# Air_Fryer_Coffee_Roaster_V1_0_2022_11_22.net
KiCad netlist of a schematic drawn in EAGLE
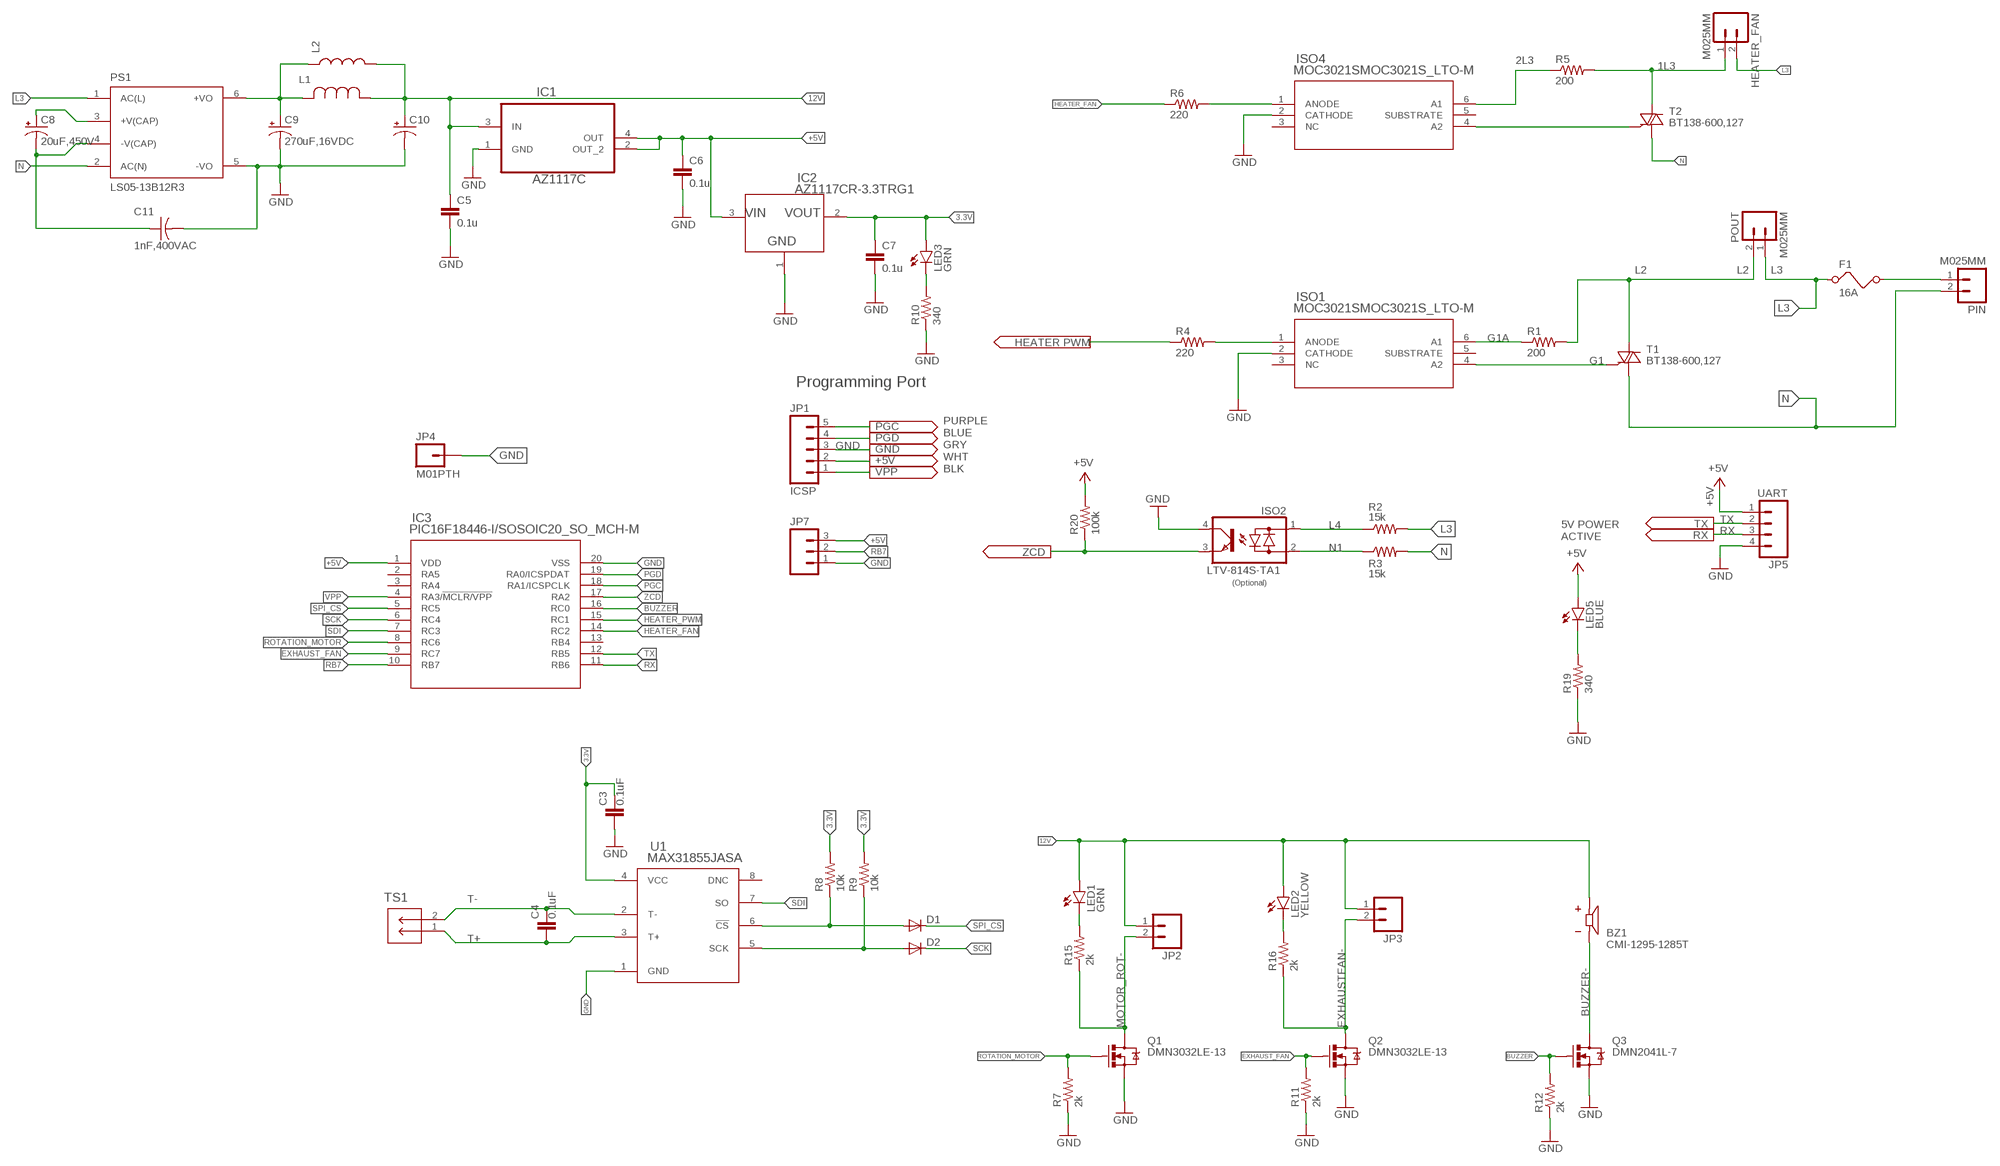
[diagram p0: schematic, sheet 1]

(export (version "E")
  (design (tool "Eeschema 10.0.6"))
  (components
    (comp (ref "BZ1")
      (value "CMI-1295-1285T")
      (footprint "eagle-import:CUI_CMI-1295-1285T")
      (fields (field (name "MF") "CUI Devices"))
      (libsource (lib "eagle-import") (part "CMI-1295-1285T"))
    )
    (comp (ref "C3")
      (value "0.1uF")
      (footprint "eagle-import:0805")
      (libsource (lib "eagle-import") (part "SparkFun-Capacitors_CAP0805"))
    )
    (comp (ref "C4")
      (value "0.1uF")
      (footprint "eagle-import:0805")
      (libsource (lib "eagle-import") (part "SparkFun-Capacitors_CAP0805"))
    )
    (comp (ref "C5")
      (value "0.1u")
      (footprint "eagle-import:1206")
      (libsource (lib "eagle-import") (part "CAP1206"))
    )
    (comp (ref "C6")
      (value "0.1u")
      (footprint "eagle-import:1206")
      (libsource (lib "eagle-import") (part "CAP1206"))
    )
    (comp (ref "C7")
      (value "0.1u")
      (footprint "eagle-import:1206")
      (libsource (lib "eagle-import") (part "CAP1206"))
    )
    (comp (ref "C8")
      (value "20uF,450V")
      (footprint "eagle-import:E5-13")
      (libsource (lib "eagle-import") (part "CPOL-USE5-13"))
    )
    (comp (ref "C9")
      (value "270uF,16VDC")
      (footprint "eagle-import:PANASONIC_E")
      (libsource (lib "eagle-import") (part "CAP_POLE"))
    )
    (comp (ref "C10")
      (value "CAP_POLE")
      (footprint "eagle-import:PANASONIC_E")
      (libsource (lib "eagle-import") (part "CAP_POLE"))
    )
    (comp (ref "C11")
      (value "1nF,400VAC")
      (footprint "eagle-import:C050-075X075")
      (libsource (lib "eagle-import") (part "C-US050-075X075"))
    )
    (comp (ref "D1")
      (value "DIODESOD-323F")
      (footprint "eagle-import:SOD-323F")
      (libsource (lib "eagle-import") (part "DIODESOD-323F"))
    )
    (comp (ref "D2")
      (value "DIODESOD-323F")
      (footprint "eagle-import:SOD-323F")
      (libsource (lib "eagle-import") (part "DIODESOD-323F"))
    )
    (comp (ref "F1")
      (value "16A")
      (footprint "eagle-import:FUSE")
      (libsource (lib "eagle-import") (part "FUSE"))
    )
    (comp (ref "HEATER_FAN")
      (value "M025MM")
      (footprint "eagle-import:SCREWTERMINAL-5MM-2")
      (libsource (lib "eagle-import") (part "SparkFun-Connectors_M025MM"))
    )
    (comp (ref "IC1")
      (value "AZ1117C")
      (footprint "eagle-import:SOT230P700X180-4N")
      (fields (field (name "MPN") "ADP3338AKCZ-5-R7"))
      (libsource (lib "eagle-import") (part "ADP3338AKCZ-5-R7"))
    )
    (comp (ref "IC2")
      (value "AZ1117CR-3.3TRG1")
      (footprint "eagle-import:SOT89_AZ1117_DIO")
      (fields (field (name "COPYRIGHT") "Copyright (C) 2022 Ultra Librarian. All rights reserved."))
      (libsource (lib "eagle-import") (part "AZ1117CR-3.3TRG1"))
    )
    (comp (ref "IC3")
      (value "PIC16F18446-I/SOSOIC20_SO_MCH-M")
      (footprint "eagle-import:SOIC20_SO_MCH-M")
      (fields
        (field (name "MANUFACTURER_PART_NUMBER") "PIC16F18446-I/SO")
        (field (name "COPYRIGHT") "Copyright (C) 2022 Ultra Librarian. All rights reserved.")
      )
      (libsource (lib "eagle-import") (part "PIC16F18446-I/SOSOIC20_SO_MCH-M"))
    )
    (comp (ref "ISO1")
      (value "MOC3021SMOC3021S_LTO-M")
      (footprint "eagle-import:MOC3021S_LTO-M")
      (fields
        (field (name "MANUFACTURER_PART_NUMBER") "MOC3021S")
        (field (name "COPYRIGHT") "Copyright (C) 2018 Accelerated Designs. All rights reserved")
      )
      (libsource (lib "eagle-import") (part "MOC3021SMOC3021S_LTO-M"))
    )
    (comp (ref "ISO2")
      (value "LTV-814S-TA1")
      (footprint "eagle-import:DIL4-SMD")
      (fields (field (name "MF") "VISHAY/TELEFUNKEN") (field (name "MPN") "SFH6206-3"))
      (libsource (lib "eagle-import") (part "SFH6206"))
    )
    (comp (ref "ISO4")
      (value "MOC3021SMOC3021S_LTO-M")
      (footprint "eagle-import:MOC3021S_LTO-M")
      (fields
        (field (name "MANUFACTURER_PART_NUMBER") "MOC3021S")
        (field (name "COPYRIGHT") "Copyright (C) 2018 Accelerated Designs. All rights reserved")
      )
      (libsource (lib "eagle-import") (part "MOC3021SMOC3021S_LTO-M"))
    )
    (comp (ref "JP1")
      (value "ICSP")
      (footprint "eagle-import:1X05")
      (libsource (lib "eagle-import") (part "M05PTH"))
    )
    (comp (ref "JP2")
      (value "M02POLAR_LOCK")
      (footprint "eagle-import:MOLEX-1X2_LOCK")
      (libsource (lib "eagle-import") (part "M02POLAR_LOCK"))
    )
    (comp (ref "JP3")
      (value "M02POLAR_LOCK")
      (footprint "eagle-import:MOLEX-1X2_LOCK")
      (libsource (lib "eagle-import") (part "M02POLAR_LOCK"))
    )
    (comp (ref "JP4")
      (value "M01PTH")
      (footprint "eagle-import:1X01")
      (libsource (lib "eagle-import") (part "M01PTH"))
    )
    (comp (ref "JP5")
      (value "UART")
      (footprint "eagle-import:1X04_LOCK")
      (libsource (lib "eagle-import") (part "M04LOCK"))
    )
    (comp (ref "JP7")
      (value "M03LOCK")
      (footprint "eagle-import:1X03_LOCK")
      (libsource (lib "eagle-import") (part "M03LOCK"))
    )
    (comp (ref "L1")
      (value "4.7uH, 2.2A")
      (footprint "eagle-import:IND_BOURNS_SRR1260")
      (fields
        (field (name "MANUFACTURER_PART_NUMBER") "SRR1260-100M")
        (field (name "COPYRIGHT") "Copyright (C) 2021 Ultra Librarian. All rights reserved.")
      )
      (libsource (lib "eagle-import") (part "SRR1260-100M"))
    )
    (comp (ref "L2")
      (value "INDUCTORCR54")
      (footprint "eagle-import:CR54")
      (libsource (lib "eagle-import") (part "INDUCTORCR54"))
    )
    (comp (ref "LED1")
      (value "GRN")
      (footprint "eagle-import:LED-1206")
      (libsource (lib "eagle-import") (part "LED1206"))
    )
    (comp (ref "LED2")
      (value "YELLOW")
      (footprint "eagle-import:LED-1206")
      (libsource (lib "eagle-import") (part "LED1206"))
    )
    (comp (ref "LED3")
      (value "GRN")
      (footprint "eagle-import:LED-1206")
      (libsource (lib "eagle-import") (part "LED1206"))
    )
    (comp (ref "LED5")
      (value "BLUE")
      (footprint "eagle-import:LED-1206")
      (libsource (lib "eagle-import") (part "LED1206"))
    )
    (comp (ref "PIN")
      (value "M025MM")
      (footprint "eagle-import:SCREWTERMINAL-5MM-2")
      (libsource (lib "eagle-import") (part "SparkFun-Connectors_M025MM"))
    )
    (comp (ref "POUT")
      (value "M025MM")
      (footprint "eagle-import:SCREWTERMINAL-5MM-2")
      (libsource (lib "eagle-import") (part "SparkFun-Connectors_M025MM"))
    )
    (comp (ref "PS1")
      (value "LS05-13B12R3")
      (footprint "eagle-import:CONV_LS05-13B12R3")
      (fields
        (field (name "DIGI-KEY_PART_NUMBER") "2725-LS05-13B12R3-ND")
        (field (name "MF") "Mornsun America, LLC")
      )
      (libsource (lib "eagle-import") (part "LS05-13B12R3"))
    )
    (comp (ref "Q1")
      (value "DMN3032LE-13")
      (footprint "eagle-import:SOT223")
      (libsource (lib "eagle-import") (part "NFET_SOT_223"))
    )
    (comp (ref "Q2")
      (value "DMN3032LE-13")
      (footprint "eagle-import:SOT223")
      (libsource (lib "eagle-import") (part "NFET_SOT_223"))
    )
    (comp (ref "Q3")
      (value "DMN2041L-7")
      (footprint "eagle-import:SOT23-3")
      (libsource (lib "eagle-import") (part "MOSFET-NCHANNELBSS123LT1G"))
    )
    (comp (ref "R1")
      (value "200")
      (footprint "eagle-import:R2512")
      (libsource (lib "eagle-import") (part "rcl_334_R-US_R2512"))
    )
    (comp (ref "R2")
      (value "15k")
      (footprint "eagle-import:R2512")
      (libsource (lib "eagle-import") (part "rcl_334_R-US_R2512"))
    )
    (comp (ref "R3")
      (value "15k")
      (footprint "eagle-import:R2512")
      (libsource (lib "eagle-import") (part "rcl_334_R-US_R2512"))
    )
    (comp (ref "R4")
      (value "220")
      (footprint "eagle-import:1206")
      (libsource (lib "eagle-import") (part "RESISTOR1206"))
    )
    (comp (ref "R5")
      (value "200")
      (footprint "eagle-import:R2512")
      (libsource (lib "eagle-import") (part "rcl_334_R-US_R2512"))
    )
    (comp (ref "R6")
      (value "220")
      (footprint "eagle-import:1206")
      (libsource (lib "eagle-import") (part "RESISTOR1206"))
    )
    (comp (ref "R7")
      (value "2k")
      (footprint "eagle-import:1206")
      (libsource (lib "eagle-import") (part "RESISTOR1206"))
    )
    (comp (ref "R8")
      (value "10k")
      (footprint "eagle-import:M0805")
      (libsource (lib "eagle-import") (part "R-US_M0805"))
    )
    (comp (ref "R9")
      (value "10k")
      (footprint "eagle-import:M0805")
      (libsource (lib "eagle-import") (part "R-US_M0805"))
    )
    (comp (ref "R10")
      (value "340")
      (footprint "eagle-import:1206")
      (libsource (lib "eagle-import") (part "RESISTOR1206"))
    )
    (comp (ref "R11")
      (value "2k")
      (footprint "eagle-import:1206")
      (libsource (lib "eagle-import") (part "RESISTOR1206"))
    )
    (comp (ref "R12")
      (value "2k")
      (footprint "eagle-import:1206")
      (libsource (lib "eagle-import") (part "RESISTOR1206"))
    )
    (comp (ref "R15")
      (value "2k")
      (footprint "eagle-import:1206")
      (libsource (lib "eagle-import") (part "RESISTOR1206"))
    )
    (comp (ref "R16")
      (value "2k")
      (footprint "eagle-import:1206")
      (libsource (lib "eagle-import") (part "RESISTOR1206"))
    )
    (comp (ref "R19")
      (value "340")
      (footprint "eagle-import:1206")
      (libsource (lib "eagle-import") (part "RESISTOR1206"))
    )
    (comp (ref "R20")
      (value "100k")
      (footprint "eagle-import:1206")
      (libsource (lib "eagle-import") (part "RESISTOR1206"))
    )
    (comp (ref "T1")
      (value "BT138-600,127")
      (footprint "eagle-import:TO220BV")
      (libsource (lib "eagle-import") (part "BT138-V"))
    )
    (comp (ref "T2")
      (value "BT138-600,127")
      (footprint "eagle-import:TO220BV")
      (libsource (lib "eagle-import") (part "BT138-V"))
    )
    (comp (ref "TS1")
      (value "YK3210203000G")
      (footprint "eagle-import:CONN2_282845-2_TEC")
      (fields
        (field (name "MANUFACTURER_PART_NUMBER") "282845-2")
        (field (name "COPYRIGHT") "Copyright (C) 2022 Ultra Librarian. All rights reserved.")
      )
      (libsource (lib "eagle-import") (part "282845-2"))
    )
    (comp (ref "U1")
      (value "MAX31855JASA")
      (footprint "eagle-import:21-0041B_8_MXM-M")
      (fields
        (field (name "MANUFACTURER_PART_NUMBER") "MAX31855JASA+")
        (field (name "COPYRIGHT") "Copyright (C) 2022 Ultra Librarian. All rights reserved.")
      )
      (libsource (lib "eagle-import") (part "MAX31855JASA+21-0041B_8_MXM-M"))
    )
  )
  (nets
    (net (code "1") (name "+5V") (class "Default")
      (node (ref "C6") (pin "1") (pinfunction "1_1") (pintype "passive"))
      (node (ref "IC1") (pin "2") (pinfunction "OUT_2_2") (pintype "output"))
      (node (ref "IC1") (pin "4") (pinfunction "OUT_4") (pintype "output"))
      (node (ref "IC2") (pin "3") (pinfunction "INPUT_3") (pintype "input"))
      (node (ref "IC3") (pin "1") (pinfunction "VDD_1") (pintype "power_in"))
      (node (ref "JP1") (pin "2") (pinfunction "2_2") (pintype "passive"))
      (node (ref "JP5") (pin "1") (pinfunction "1_1") (pintype "passive"))
      (node (ref "JP7") (pin "3") (pinfunction "3_3") (pintype "passive"))
      (node (ref "LED5") (pin "A") (pinfunction "A_A") (pintype "passive"))
      (node (ref "R20") (pin "2") (pinfunction "2_2") (pintype "passive"))
    )
    (net (code "2") (name "1L3") (class "Default")
      (node (ref "HEATER_FAN") (pin "1") (pinfunction "1_1") (pintype "passive"))
      (node (ref "R5") (pin "2") (pinfunction "2_2") (pintype "passive"))
      (node (ref "T2") (pin "T2") (pinfunction "A2_T2") (pintype "passive"))
    )
    (net (code "3") (name "2L3") (class "Default")
      (node (ref "ISO4") (pin "6") (pinfunction "A1_6") (pintype "passive"))
      (node (ref "R5") (pin "1") (pinfunction "1_1") (pintype "passive"))
    )
    (net (code "4") (name "3.3V") (class "Default")
      (node (ref "C3") (pin "2") (pinfunction "2_2") (pintype "passive"))
      (node (ref "C7") (pin "1") (pinfunction "1_1") (pintype "passive"))
      (node (ref "IC2") (pin "2") (pinfunction "OUTPUT_2") (pintype "output"))
      (node (ref "LED3") (pin "A") (pinfunction "A_A") (pintype "passive"))
      (node (ref "R8") (pin "2") (pinfunction "2_2") (pintype "passive"))
      (node (ref "R9") (pin "2") (pinfunction "2_2") (pintype "passive"))
      (node (ref "U1") (pin "4") (pinfunction "VCC_4") (pintype "power_in"))
    )
    (net (code "5") (name "12V") (class "Default")
      (node (ref "BZ1") (pin "P") (pinfunction "P_P") (pintype "passive"))
      (node (ref "C10") (pin "+") (pinfunction "+_+") (pintype "passive"))
      (node (ref "C5") (pin "1") (pinfunction "1_1") (pintype "passive"))
      (node (ref "IC1") (pin "3") (pinfunction "IN_3") (pintype "input"))
      (node (ref "JP2") (pin "1") (pinfunction "1_1") (pintype "passive"))
      (node (ref "JP3") (pin "1") (pinfunction "1_1") (pintype "passive"))
      (node (ref "L1") (pin "1") (pinfunction "1_1") (pintype "passive"))
      (node (ref "L2") (pin "P$2") (pinfunction "2_P$2") (pintype "passive"))
      (node (ref "LED1") (pin "A") (pinfunction "A_A") (pintype "passive"))
      (node (ref "LED2") (pin "A") (pinfunction "A_A") (pintype "passive"))
    )
    (net (code "6") (name "BUZZER") (class "Default")
      (node (ref "IC3") (pin "16") (pinfunction "RC0_16") (pintype "bidirectional"))
      (node (ref "Q3") (pin "1") (pinfunction "G_1") (pintype "passive"))
      (node (ref "R12") (pin "2") (pinfunction "2_2") (pintype "passive"))
    )
    (net (code "7") (name "BUZZER-") (class "Default")
      (node (ref "BZ1") (pin "N") (pinfunction "N_N") (pintype "passive"))
      (node (ref "Q3") (pin "3") (pinfunction "D_3") (pintype "passive"))
    )
    (net (code "8") (name "EXHAUSTFAN-") (class "Default")
      (node (ref "JP3") (pin "2") (pinfunction "2_2") (pintype "passive"))
      (node (ref "Q2") (pin "2") (pinfunction "D_2") (pintype "passive"))
      (node (ref "Q2") (pin "4") (pinfunction "D_4") (pintype "passive"))
      (node (ref "R16") (pin "1") (pinfunction "1_1") (pintype "passive"))
    )
    (net (code "9") (name "EXHAUST_FAN") (class "Default")
      (node (ref "IC3") (pin "9") (pinfunction "RC7_9") (pintype "bidirectional"))
      (node (ref "Q2") (pin "1") (pinfunction "G_1") (pintype "passive"))
      (node (ref "R11") (pin "2") (pinfunction "2_2") (pintype "passive"))
    )
    (net (code "10") (name "G1") (class "Default")
      (node (ref "ISO1") (pin "4") (pinfunction "A2_4") (pintype "passive"))
      (node (ref "T1") (pin "G") (pinfunction "G_G") (pintype "passive"))
    )
    (net (code "11") (name "G1A") (class "Default")
      (node (ref "ISO1") (pin "6") (pinfunction "A1_6") (pintype "passive"))
      (node (ref "R1") (pin "1") (pinfunction "1_1") (pintype "passive"))
    )
    (net (code "12") (name "GND") (class "Default")
      (node (ref "C10") (pin "-") (pinfunction "-_-") (pintype "passive"))
      (node (ref "C11") (pin "2") (pinfunction "2_2") (pintype "passive"))
      (node (ref "C3") (pin "1") (pinfunction "1_1") (pintype "passive"))
      (node (ref "C5") (pin "2") (pinfunction "2_2") (pintype "passive"))
      (node (ref "C6") (pin "2") (pinfunction "2_2") (pintype "passive"))
      (node (ref "C7") (pin "2") (pinfunction "2_2") (pintype "passive"))
      (node (ref "C9") (pin "-") (pinfunction "-_-") (pintype "passive"))
      (node (ref "IC1") (pin "1") (pinfunction "GND_1") (pintype "passive"))
      (node (ref "IC2") (pin "1") (pinfunction "ADJ/GND_1") (pintype "passive"))
      (node (ref "IC3") (pin "20") (pinfunction "VSS_20") (pintype "passive"))
      (node (ref "ISO1") (pin "2") (pinfunction "CATHODE_2") (pintype "passive"))
      (node (ref "ISO2") (pin "4") (pinfunction "C_4") (pintype "passive"))
      (node (ref "ISO4") (pin "2") (pinfunction "CATHODE_2") (pintype "passive"))
      (node (ref "JP1") (pin "3") (pinfunction "3_3") (pintype "passive"))
      (node (ref "JP4") (pin "1") (pinfunction "1_1") (pintype "passive"))
      (node (ref "JP5") (pin "4") (pinfunction "4_4") (pintype "passive"))
      (node (ref "JP7") (pin "1") (pinfunction "1_1") (pintype "passive"))
      (node (ref "PS1") (pin "5") (pinfunction "-VO_5") (pintype "output"))
      (node (ref "Q1") (pin "3") (pinfunction "S_3") (pintype "passive"))
      (node (ref "Q2") (pin "3") (pinfunction "S_3") (pintype "passive"))
      (node (ref "Q3") (pin "2") (pinfunction "S_2") (pintype "passive"))
      (node (ref "R10") (pin "1") (pinfunction "1_1") (pintype "passive"))
      (node (ref "R11") (pin "1") (pinfunction "1_1") (pintype "passive"))
      (node (ref "R12") (pin "1") (pinfunction "1_1") (pintype "passive"))
      (node (ref "R19") (pin "1") (pinfunction "1_1") (pintype "passive"))
      (node (ref "R7") (pin "1") (pinfunction "1_1") (pintype "passive"))
      (node (ref "U1") (pin "1") (pinfunction "GND_1") (pintype "power_in"))
    )
    (net (code "13") (name "HEATER_FAN") (class "Default")
      (node (ref "IC3") (pin "14") (pinfunction "RC2_14") (pintype "bidirectional"))
      (node (ref "R6") (pin "1") (pinfunction "1_1") (pintype "passive"))
    )
    (net (code "14") (name "HEATER_PWM") (class "Default")
      (node (ref "IC3") (pin "15") (pinfunction "RC1_15") (pintype "bidirectional"))
      (node (ref "R4") (pin "1") (pinfunction "1_1") (pintype "passive"))
    )
    (net (code "15") (name "L2") (class "Default")
      (node (ref "POUT") (pin "2") (pinfunction "2_2") (pintype "passive"))
      (node (ref "R1") (pin "2") (pinfunction "2_2") (pintype "passive"))
      (node (ref "T1") (pin "T2") (pinfunction "A2_T2") (pintype "passive"))
    )
    (net (code "16") (name "L3") (class "Default")
      (node (ref "F1") (pin "1") (pinfunction "1_1") (pintype "passive"))
      (node (ref "HEATER_FAN") (pin "2") (pinfunction "2_2") (pintype "passive"))
      (node (ref "POUT") (pin "1") (pinfunction "1_1") (pintype "passive"))
      (node (ref "PS1") (pin "1") (pinfunction "AC(L)_1") (pintype "input"))
      (node (ref "R2") (pin "2") (pinfunction "2_2") (pintype "passive"))
    )
    (net (code "17") (name "L4") (class "Default")
      (node (ref "ISO2") (pin "1") (pinfunction "AC1_1") (pintype "passive"))
      (node (ref "R2") (pin "1") (pinfunction "1_1") (pintype "passive"))
    )
    (net (code "18") (name "MOTOR_ROT-") (class "Default")
      (node (ref "JP2") (pin "2") (pinfunction "2_2") (pintype "passive"))
      (node (ref "Q1") (pin "2") (pinfunction "D_2") (pintype "passive"))
      (node (ref "Q1") (pin "4") (pinfunction "D_4") (pintype "passive"))
      (node (ref "R15") (pin "1") (pinfunction "1_1") (pintype "passive"))
    )
    (net (code "19") (name "N") (class "Default")
      (node (ref "PIN") (pin "2") (pinfunction "2_2") (pintype "passive"))
      (node (ref "PS1") (pin "2") (pinfunction "AC(N)_2") (pintype "input"))
      (node (ref "R3") (pin "2") (pinfunction "2_2") (pintype "passive"))
      (node (ref "T1") (pin "T1") (pinfunction "A1_T1") (pintype "passive"))
      (node (ref "T2") (pin "T1") (pinfunction "A1_T1") (pintype "passive"))
    )
    (net (code "20") (name "N1") (class "Default")
      (node (ref "ISO2") (pin "2") (pinfunction "AC2_2") (pintype "passive"))
      (node (ref "R3") (pin "1") (pinfunction "1_1") (pintype "passive"))
    )
    (net (code "21") (name "Net-(F1-Pad2)") (class "Default")
      (node (ref "F1") (pin "2") (pinfunction "2_2") (pintype "passive"))
      (node (ref "PIN") (pin "1") (pinfunction "1_1") (pintype "passive"))
    )
    (net (code "22") (name "Net-(ISO1-ANODE)") (class "Default")
      (node (ref "ISO1") (pin "1") (pinfunction "ANODE_1") (pintype "passive"))
      (node (ref "R4") (pin "2") (pinfunction "2_2") (pintype "passive"))
    )
    (net (code "23") (name "Net-(ISO4-A2)") (class "Default")
      (node (ref "ISO4") (pin "4") (pinfunction "A2_4") (pintype "passive"))
      (node (ref "T2") (pin "G") (pinfunction "G_G") (pintype "passive"))
    )
    (net (code "24") (name "Net-(ISO4-ANODE)") (class "Default")
      (node (ref "ISO4") (pin "1") (pinfunction "ANODE_1") (pintype "passive"))
      (node (ref "R6") (pin "2") (pinfunction "2_2") (pintype "passive"))
    )
    (net (code "25") (name "Net-(L2-1)") (class "Default")
      (node (ref "C9") (pin "+") (pinfunction "+_+") (pintype "passive"))
      (node (ref "L1") (pin "2") (pinfunction "2_2") (pintype "passive"))
      (node (ref "L2") (pin "P$1") (pinfunction "1_P$1") (pintype "passive"))
      (node (ref "PS1") (pin "6") (pinfunction "+VO_6") (pintype "output"))
    )
    (net (code "26") (name "Net-(LED1-PadC)") (class "Default")
      (node (ref "LED1") (pin "C") (pinfunction "C_C") (pintype "passive"))
      (node (ref "R15") (pin "2") (pinfunction "2_2") (pintype "passive"))
    )
    (net (code "27") (name "Net-(LED2-PadC)") (class "Default")
      (node (ref "LED2") (pin "C") (pinfunction "C_C") (pintype "passive"))
      (node (ref "R16") (pin "2") (pinfunction "2_2") (pintype "passive"))
    )
    (net (code "28") (name "Net-(LED3-PadC)") (class "Default")
      (node (ref "LED3") (pin "C") (pinfunction "C_C") (pintype "passive"))
      (node (ref "R10") (pin "2") (pinfunction "2_2") (pintype "passive"))
    )
    (net (code "29") (name "Net-(LED5-PadC)") (class "Default")
      (node (ref "LED5") (pin "C") (pinfunction "C_C") (pintype "passive"))
      (node (ref "R19") (pin "2") (pinfunction "2_2") (pintype "passive"))
    )
    (net (code "30") (name "Net-(PS1-+V(CAP))") (class "Default")
      (node (ref "C8") (pin "+") (pinfunction "+_+") (pintype "passive"))
      (node (ref "PS1") (pin "3") (pinfunction "+V(CAP)_3") (pintype "passive"))
    )
    (net (code "31") (name "Net-(PS1--V(CAP))") (class "Default")
      (node (ref "C11") (pin "1") (pinfunction "1_1") (pintype "passive"))
      (node (ref "C8") (pin "-") (pinfunction "-_-") (pintype "passive"))
      (node (ref "PS1") (pin "4") (pinfunction "-V(CAP)_4") (pintype "passive"))
    )
    (net (code "32") (name "Net-(U1-SCK)") (class "Default")
      (node (ref "D2") (pin "A") (pinfunction "A_A") (pintype "passive"))
      (node (ref "R9") (pin "1") (pinfunction "1_1") (pintype "passive"))
      (node (ref "U1") (pin "5") (pinfunction "SCK_5") (pintype "input"))
    )
    (net (code "33") (name "Net-(U1-~{CS})") (class "Default")
      (node (ref "D1") (pin "A") (pinfunction "A_A") (pintype "passive"))
      (node (ref "R8") (pin "1") (pinfunction "1_1") (pintype "passive"))
      (node (ref "U1") (pin "6") (pinfunction "~{CS}_6") (pintype "passive"))
    )
    (net (code "34") (name "PGC") (class "Default")
      (node (ref "IC3") (pin "18") (pinfunction "RA1/ICSPCLK_18") (pintype "bidirectional"))
      (node (ref "JP1") (pin "5") (pinfunction "5_5") (pintype "passive"))
    )
    (net (code "35") (name "PGD") (class "Default")
      (node (ref "IC3") (pin "19") (pinfunction "RA0/ICSPDAT_19") (pintype "bidirectional"))
      (node (ref "JP1") (pin "4") (pinfunction "4_4") (pintype "passive"))
    )
    (net (code "36") (name "RB7") (class "Default")
      (node (ref "IC3") (pin "10") (pinfunction "RB7_10") (pintype "bidirectional"))
      (node (ref "JP7") (pin "2") (pinfunction "2_2") (pintype "passive"))
    )
    (net (code "37") (name "ROTATION_MOTOR") (class "Default")
      (node (ref "IC3") (pin "8") (pinfunction "RC6_8") (pintype "bidirectional"))
      (node (ref "Q1") (pin "1") (pinfunction "G_1") (pintype "passive"))
      (node (ref "R7") (pin "2") (pinfunction "2_2") (pintype "passive"))
    )
    (net (code "38") (name "RX") (class "Default")
      (node (ref "IC3") (pin "11") (pinfunction "RB6_11") (pintype "bidirectional"))
      (node (ref "JP5") (pin "3") (pinfunction "3_3") (pintype "passive"))
    )
    (net (code "39") (name "SCK") (class "Default")
      (node (ref "D2") (pin "C") (pinfunction "C_C") (pintype "passive"))
      (node (ref "IC3") (pin "6") (pinfunction "RC4_6") (pintype "bidirectional"))
    )
    (net (code "40") (name "SDI") (class "Default")
      (node (ref "IC3") (pin "7") (pinfunction "RC3_7") (pintype "bidirectional"))
      (node (ref "U1") (pin "7") (pinfunction "SO_7") (pintype "output"))
    )
    (net (code "41") (name "SPI_CS") (class "Default")
      (node (ref "D1") (pin "C") (pinfunction "C_C") (pintype "passive"))
      (node (ref "IC3") (pin "5") (pinfunction "RC5_5") (pintype "bidirectional"))
    )
    (net (code "42") (name "T+") (class "Default")
      (node (ref "C4") (pin "1") (pinfunction "1_1") (pintype "passive"))
      (node (ref "TS1") (pin "1") (pinfunction "1_1") (pintype "passive"))
      (node (ref "U1") (pin "3") (pinfunction "T+_3") (pintype "input"))
    )
    (net (code "43") (name "T-") (class "Default")
      (node (ref "C4") (pin "2") (pinfunction "2_2") (pintype "passive"))
      (node (ref "TS1") (pin "2") (pinfunction "2_2") (pintype "passive"))
      (node (ref "U1") (pin "2") (pinfunction "T-_2") (pintype "input"))
    )
    (net (code "44") (name "TX") (class "Default")
      (node (ref "IC3") (pin "12") (pinfunction "RB5_12") (pintype "bidirectional"))
      (node (ref "JP5") (pin "2") (pinfunction "2_2") (pintype "passive"))
    )
    (net (code "45") (name "VPP") (class "Default")
      (node (ref "IC3") (pin "4") (pinfunction "RA3/~{MCLR/VPP}_4") (pintype "bidirectional"))
      (node (ref "JP1") (pin "1") (pinfunction "1_1") (pintype "passive"))
    )
    (net (code "46") (name "ZCD") (class "Default")
      (node (ref "IC3") (pin "17") (pinfunction "RA2_17") (pintype "bidirectional"))
      (node (ref "ISO2") (pin "3") (pinfunction "E_3") (pintype "passive"))
      (node (ref "R20") (pin "1") (pinfunction "1_1") (pintype "passive"))
    )
    (net (code "47") (name "unconnected-(IC3-RA4-Pad3)") (class "Default")
      (node (ref "IC3") (pin "3") (pinfunction "RA4_3") (pintype "bidirectional"))
    )
    (net (code "48") (name "unconnected-(IC3-RA5-Pad2)") (class "Default")
      (node (ref "IC3") (pin "2") (pinfunction "RA5_2") (pintype "bidirectional"))
    )
    (net (code "49") (name "unconnected-(IC3-RB4-Pad13)") (class "Default")
      (node (ref "IC3") (pin "13") (pinfunction "RB4_13") (pintype "bidirectional"))
    )
    (net (code "50") (name "unconnected-(ISO1-NC-Pad3)") (class "Default")
      (node (ref "ISO1") (pin "3") (pinfunction "NC_3") (pintype "passive"))
    )
    (net (code "51") (name "unconnected-(ISO1-SUBSTRATE-Pad5)") (class "Default")
      (node (ref "ISO1") (pin "5") (pinfunction "SUBSTRATE_5") (pintype "passive"))
    )
    (net (code "52") (name "unconnected-(ISO4-NC-Pad3)") (class "Default")
      (node (ref "ISO4") (pin "3") (pinfunction "NC_3") (pintype "passive"))
    )
    (net (code "53") (name "unconnected-(ISO4-SUBSTRATE-Pad5)") (class "Default")
      (node (ref "ISO4") (pin "5") (pinfunction "SUBSTRATE_5") (pintype "passive"))
    )
    (net (code "54") (name "unconnected-(U1-DNC-Pad8)") (class "Default")
      (node (ref "U1") (pin "8") (pinfunction "DNC_8") (pintype "no_connect"))
    )
  )
)
